# Nova_Placa.net
KiCad netlist of a schematic drawn in EAGLE
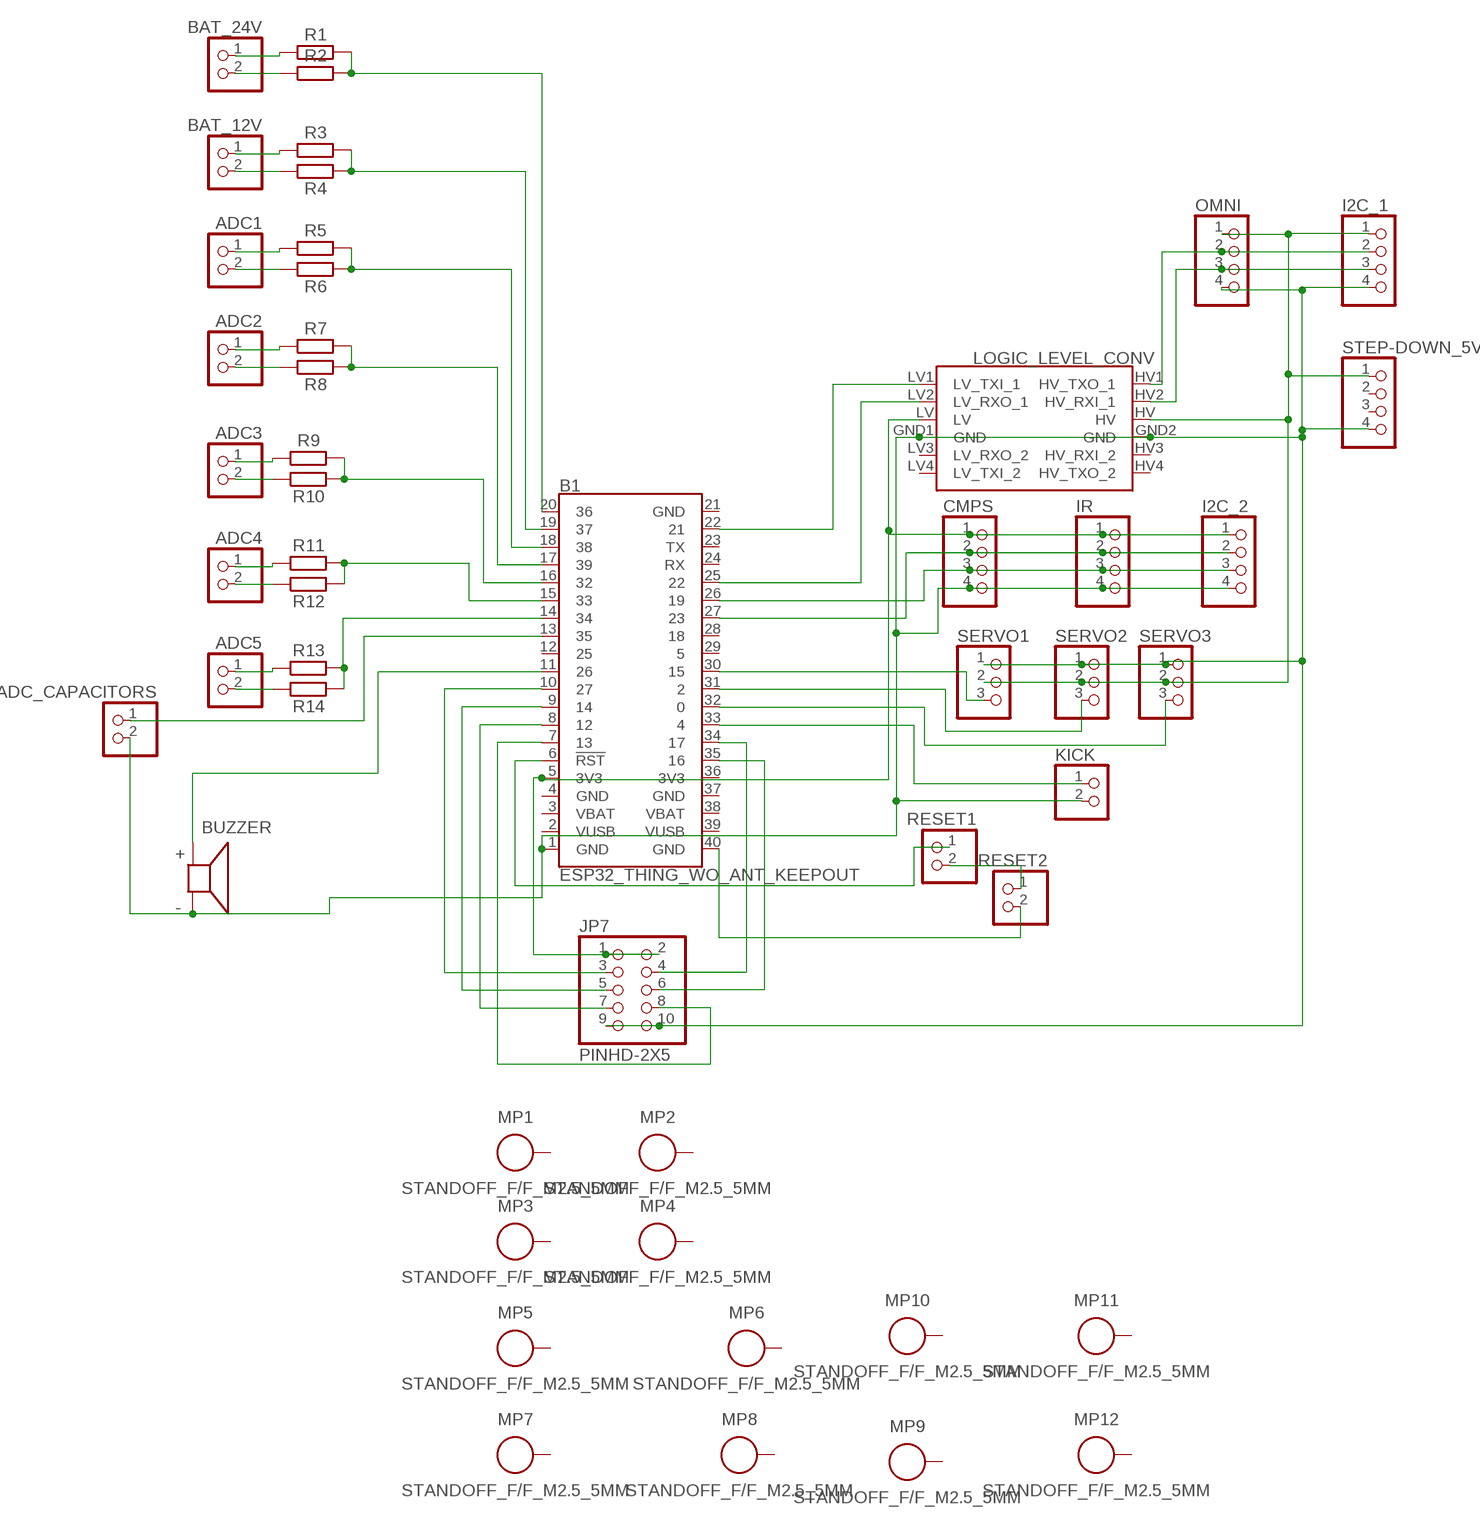
[diagram p0: schematic, sheet 1]

(export (version "E")
  (design (tool "Eeschema 10.0.6"))
  (components
    (comp (ref "ADC1")
      (value "PINHD-1X2")
      (footprint "eagle-import:1X02")
      (libsource (lib "eagle-import") (part "PINHD-1X2"))
    )
    (comp (ref "ADC2")
      (value "PINHD-1X2")
      (footprint "eagle-import:1X02")
      (libsource (lib "eagle-import") (part "PINHD-1X2"))
    )
    (comp (ref "ADC3")
      (value "PINHD-1X2")
      (footprint "eagle-import:1X02")
      (libsource (lib "eagle-import") (part "PINHD-1X2"))
    )
    (comp (ref "ADC4")
      (value "PINHD-1X2")
      (footprint "eagle-import:1X02")
      (libsource (lib "eagle-import") (part "PINHD-1X2"))
    )
    (comp (ref "ADC5")
      (value "PINHD-1X2")
      (footprint "eagle-import:1X02")
      (libsource (lib "eagle-import") (part "PINHD-1X2"))
    )
    (comp (ref "ADC_CAPACITORS")
      (value "PINHD-1X2")
      (footprint "eagle-import:1X02")
      (libsource (lib "eagle-import") (part "PINHD-1X2"))
    )
    (comp (ref "B1")
      (value "ESP32_THING_WO_ANT_KEEPOUT")
      (footprint "eagle-import:ESP32_THING_NO_ANT")
      (libsource (lib "eagle-import") (part "ESP32_THING_WO_ANT_KEEPOUT"))
    )
    (comp (ref "BAT_12V")
      (value "PINHD-1X2")
      (footprint "eagle-import:1X02")
      (libsource (lib "eagle-import") (part "PINHD-1X2"))
    )
    (comp (ref "BAT_24V")
      (value "PINHD-1X2")
      (footprint "eagle-import:1X02")
      (libsource (lib "eagle-import") (part "PINHD-1X2"))
    )
    (comp (ref "BUZZER")
      (value "AT-1220-TT-9-R")
      (footprint "eagle-import:XDCR_AT-1220-TT-9-R")
      (fields (field (name "MANUFACTURER") "PUI Audio"))
      (libsource (lib "eagle-import") (part "AT-1220-TT-9-R"))
    )
    (comp (ref "CMPS")
      (value "PINHD-1X4")
      (footprint "eagle-import:1X04")
      (libsource (lib "eagle-import") (part "PINHD-1X4"))
    )
    (comp (ref "I2C_1")
      (value "PINHD-1X4")
      (footprint "eagle-import:1X04")
      (libsource (lib "eagle-import") (part "PINHD-1X4"))
    )
    (comp (ref "I2C_2")
      (value "PINHD-1X4")
      (footprint "eagle-import:1X04")
      (libsource (lib "eagle-import") (part "PINHD-1X4"))
    )
    (comp (ref "IR")
      (value "PINHD-1X4")
      (footprint "eagle-import:1X04")
      (libsource (lib "eagle-import") (part "PINHD-1X4"))
    )
    (comp (ref "JP7")
      (value "PINHD-2X5")
      (footprint "eagle-import:2X05")
      (libsource (lib "eagle-import") (part "PINHD-2X5"))
    )
    (comp (ref "KICK")
      (value "PINHD-1X2")
      (footprint "eagle-import:1X02")
      (libsource (lib "eagle-import") (part "PINHD-1X2"))
    )
    (comp (ref "LOGIC_LEVEL_CONV")
      (value "SPARKFUN_LOGIC_LEVEL_CONVERTERLOCK")
      (footprint "eagle-import:SPARKFUN_LOGIC_LEVEL_CONVERTER_LOCK")
      (libsource (lib "eagle-import") (part "SPARKFUN_LOGIC_LEVEL_CONVERTERLOCK"))
    )
    (comp (ref "MP1")
      (value "STANDOFF_F/F_M2.5_5MM")
      (footprint "eagle-import:STANDOFF_HEX_FEMALE_500X500_M2.5X0.45_MTGP755H270")
      (libsource (lib "eagle-import") (part "STANDOFF_F/FM2.5_5MM_"))
    )
    (comp (ref "MP2")
      (value "STANDOFF_F/F_M2.5_5MM")
      (footprint "eagle-import:STANDOFF_HEX_FEMALE_500X500_M2.5X0.45_MTGP755H270")
      (libsource (lib "eagle-import") (part "STANDOFF_F/FM2.5_5MM_"))
    )
    (comp (ref "MP3")
      (value "STANDOFF_F/F_M2.5_5MM")
      (footprint "eagle-import:STANDOFF_HEX_FEMALE_500X500_M2.5X0.45_MTGP755H270")
      (libsource (lib "eagle-import") (part "STANDOFF_F/FM2.5_5MM_"))
    )
    (comp (ref "MP4")
      (value "STANDOFF_F/F_M2.5_5MM")
      (footprint "eagle-import:STANDOFF_HEX_FEMALE_500X500_M2.5X0.45_MTGP755H270")
      (libsource (lib "eagle-import") (part "STANDOFF_F/FM2.5_5MM_"))
    )
    (comp (ref "MP5")
      (value "STANDOFF_F/F_M2.5_5MM")
      (footprint "eagle-import:STANDOFF_HEX_FEMALE_500X500_M2.5X0.45_MTGP755H270")
      (libsource (lib "eagle-import") (part "STANDOFF_F/FM2.5_5MM_"))
    )
    (comp (ref "MP6")
      (value "STANDOFF_F/F_M2.5_5MM")
      (footprint "eagle-import:STANDOFF_HEX_FEMALE_500X500_M2.5X0.45_MTGP755H270")
      (libsource (lib "eagle-import") (part "STANDOFF_F/FM2.5_5MM_"))
    )
    (comp (ref "MP7")
      (value "STANDOFF_F/F_M2.5_5MM")
      (footprint "eagle-import:STANDOFF_HEX_FEMALE_500X500_M2.5X0.45_MTGP755H270")
      (libsource (lib "eagle-import") (part "STANDOFF_F/FM2.5_5MM_"))
    )
    (comp (ref "MP8")
      (value "STANDOFF_F/F_M2.5_5MM")
      (footprint "eagle-import:STANDOFF_HEX_FEMALE_500X500_M2.5X0.45_MTGP755H270")
      (libsource (lib "eagle-import") (part "STANDOFF_F/FM2.5_5MM_"))
    )
    (comp (ref "MP9")
      (value "STANDOFF_F/F_M2.5_5MM")
      (footprint "eagle-import:STANDOFF_HEX_FEMALE_500X500_M2.5X0.45_MTGP755H270")
      (libsource (lib "eagle-import") (part "STANDOFF_F/FM2.5_5MM_"))
    )
    (comp (ref "MP10")
      (value "STANDOFF_F/F_M2.5_5MM")
      (footprint "eagle-import:STANDOFF_HEX_FEMALE_500X500_M2.5X0.45_MTGP755H270")
      (libsource (lib "eagle-import") (part "STANDOFF_F/FM2.5_5MM_"))
    )
    (comp (ref "MP11")
      (value "STANDOFF_F/F_M2.5_5MM")
      (footprint "eagle-import:STANDOFF_HEX_FEMALE_500X500_M2.5X0.45_MTGP755H270")
      (libsource (lib "eagle-import") (part "STANDOFF_F/FM2.5_5MM_"))
    )
    (comp (ref "MP12")
      (value "STANDOFF_F/F_M2.5_5MM")
      (footprint "eagle-import:STANDOFF_HEX_FEMALE_500X500_M2.5X0.45_MTGP755H270")
      (libsource (lib "eagle-import") (part "STANDOFF_F/FM2.5_5MM_"))
    )
    (comp (ref "OMNI")
      (value "PINHD-1X4")
      (footprint "eagle-import:1X04")
      (libsource (lib "eagle-import") (part "PINHD-1X4"))
    )
    (comp (ref "R1")
      (value "R_AXIAL-7.2MM-PITCH")
      (footprint "eagle-import:RESAD724W46L381D178B")
      (libsource (lib "eagle-import") (part "RAXIAL-7.2MM-PITCH_"))
    )
    (comp (ref "R2")
      (value "R_AXIAL-7.2MM-PITCH")
      (footprint "eagle-import:RESAD724W46L381D178B")
      (libsource (lib "eagle-import") (part "RAXIAL-7.2MM-PITCH_"))
    )
    (comp (ref "R3")
      (value "R_AXIAL-7.2MM-PITCH")
      (footprint "eagle-import:RESAD724W46L381D178B")
      (libsource (lib "eagle-import") (part "RAXIAL-7.2MM-PITCH_"))
    )
    (comp (ref "R4")
      (value "R_AXIAL-7.2MM-PITCH")
      (footprint "eagle-import:RESAD724W46L381D178B")
      (libsource (lib "eagle-import") (part "RAXIAL-7.2MM-PITCH_"))
    )
    (comp (ref "R5")
      (value "R_AXIAL-7.2MM-PITCH")
      (footprint "eagle-import:RESAD724W46L381D178B")
      (libsource (lib "eagle-import") (part "RAXIAL-7.2MM-PITCH_"))
    )
    (comp (ref "R6")
      (value "R_AXIAL-7.2MM-PITCH")
      (footprint "eagle-import:RESAD724W46L381D178B")
      (libsource (lib "eagle-import") (part "RAXIAL-7.2MM-PITCH_"))
    )
    (comp (ref "R7")
      (value "R_AXIAL-7.2MM-PITCH")
      (footprint "eagle-import:RESAD724W46L381D178B")
      (libsource (lib "eagle-import") (part "RAXIAL-7.2MM-PITCH_"))
    )
    (comp (ref "R8")
      (value "R_AXIAL-7.2MM-PITCH")
      (footprint "eagle-import:RESAD724W46L381D178B")
      (libsource (lib "eagle-import") (part "RAXIAL-7.2MM-PITCH_"))
    )
    (comp (ref "R9")
      (value "R_AXIAL-7.2MM-PITCH")
      (footprint "eagle-import:RESAD724W46L381D178B")
      (libsource (lib "eagle-import") (part "RAXIAL-7.2MM-PITCH_"))
    )
    (comp (ref "R10")
      (value "R_AXIAL-7.2MM-PITCH")
      (footprint "eagle-import:RESAD724W46L381D178B")
      (libsource (lib "eagle-import") (part "RAXIAL-7.2MM-PITCH_"))
    )
    (comp (ref "R11")
      (value "R_AXIAL-7.2MM-PITCH")
      (footprint "eagle-import:RESAD724W46L381D178B")
      (libsource (lib "eagle-import") (part "RAXIAL-7.2MM-PITCH_"))
    )
    (comp (ref "R12")
      (value "R_AXIAL-7.2MM-PITCH")
      (footprint "eagle-import:RESAD724W46L381D178B")
      (libsource (lib "eagle-import") (part "RAXIAL-7.2MM-PITCH_"))
    )
    (comp (ref "R13")
      (value "R_AXIAL-7.2MM-PITCH")
      (footprint "eagle-import:RESAD724W46L381D178B")
      (libsource (lib "eagle-import") (part "RAXIAL-7.2MM-PITCH_"))
    )
    (comp (ref "R14")
      (value "R_AXIAL-7.2MM-PITCH")
      (footprint "eagle-import:RESAD724W46L381D178B")
      (libsource (lib "eagle-import") (part "RAXIAL-7.2MM-PITCH_"))
    )
    (comp (ref "RESET1")
      (value "PINHD-1X2")
      (footprint "eagle-import:1X02")
      (libsource (lib "eagle-import") (part "PINHD-1X2"))
    )
    (comp (ref "RESET2")
      (value "PINHD-1X2")
      (footprint "eagle-import:1X02")
      (libsource (lib "eagle-import") (part "PINHD-1X2"))
    )
    (comp (ref "SERVO1")
      (value "PINHD-1X3")
      (footprint "eagle-import:1X03")
      (libsource (lib "eagle-import") (part "PINHD-1X3"))
    )
    (comp (ref "SERVO2")
      (value "PINHD-1X3")
      (footprint "eagle-import:1X03")
      (libsource (lib "eagle-import") (part "PINHD-1X3"))
    )
    (comp (ref "SERVO3")
      (value "PINHD-1X3")
      (footprint "eagle-import:1X03")
      (libsource (lib "eagle-import") (part "PINHD-1X3"))
    )
    (comp (ref "STEP-DOWN_5V")
      (value "PINHD-1X4")
      (footprint "eagle-import:1X04")
      (libsource (lib "eagle-import") (part "PINHD-1X4"))
    )
  )
  (nets
    (net (code "1") (name "Net-(ADC1-Pad1)") (class "Default")
      (node (ref "ADC1") (pin "1") (pinfunction "1_1") (pintype "passive"))
      (node (ref "R5") (pin "1") (pinfunction "1_1") (pintype "passive"))
    )
    (net (code "2") (name "Net-(ADC1-Pad2)") (class "Default")
      (node (ref "ADC1") (pin "2") (pinfunction "2_2") (pintype "passive"))
      (node (ref "R6") (pin "1") (pinfunction "1_1") (pintype "passive"))
    )
    (net (code "3") (name "Net-(ADC2-Pad1)") (class "Default")
      (node (ref "ADC2") (pin "1") (pinfunction "1_1") (pintype "passive"))
      (node (ref "R7") (pin "1") (pinfunction "1_1") (pintype "passive"))
    )
    (net (code "4") (name "Net-(ADC2-Pad2)") (class "Default")
      (node (ref "ADC2") (pin "2") (pinfunction "2_2") (pintype "passive"))
      (node (ref "R8") (pin "1") (pinfunction "1_1") (pintype "passive"))
    )
    (net (code "5") (name "Net-(ADC3-Pad1)") (class "Default")
      (node (ref "ADC3") (pin "1") (pinfunction "1_1") (pintype "passive"))
      (node (ref "R9") (pin "1") (pinfunction "1_1") (pintype "passive"))
    )
    (net (code "6") (name "Net-(ADC3-Pad2)") (class "Default")
      (node (ref "ADC3") (pin "2") (pinfunction "2_2") (pintype "passive"))
      (node (ref "R10") (pin "1") (pinfunction "1_1") (pintype "passive"))
    )
    (net (code "7") (name "Net-(ADC4-Pad1)") (class "Default")
      (node (ref "ADC4") (pin "1") (pinfunction "1_1") (pintype "passive"))
      (node (ref "R11") (pin "1") (pinfunction "1_1") (pintype "passive"))
    )
    (net (code "8") (name "Net-(ADC4-Pad2)") (class "Default")
      (node (ref "ADC4") (pin "2") (pinfunction "2_2") (pintype "passive"))
      (node (ref "R12") (pin "1") (pinfunction "1_1") (pintype "passive"))
    )
    (net (code "9") (name "Net-(ADC5-Pad1)") (class "Default")
      (node (ref "ADC5") (pin "1") (pinfunction "1_1") (pintype "passive"))
      (node (ref "R13") (pin "1") (pinfunction "1_1") (pintype "passive"))
    )
    (net (code "10") (name "Net-(ADC5-Pad2)") (class "Default")
      (node (ref "ADC5") (pin "2") (pinfunction "2_2") (pintype "passive"))
      (node (ref "R14") (pin "1") (pinfunction "1_1") (pintype "passive"))
    )
    (net (code "11") (name "Net-(ADC_CAPACITORS-Pad2)") (class "Default")
      (node (ref "ADC_CAPACITORS") (pin "2") (pinfunction "2_2") (pintype "passive"))
      (node (ref "B1") (pin "1") (pinfunction "GND_1") (pintype "bidirectional"))
      (node (ref "BUZZER") (pin "N") (pinfunction "N_N") (pintype "passive"))
      (node (ref "CMPS") (pin "4") (pinfunction "4_4") (pintype "passive"))
      (node (ref "I2C_1") (pin "4") (pinfunction "4_4") (pintype "passive"))
      (node (ref "I2C_2") (pin "4") (pinfunction "4_4") (pintype "passive"))
      (node (ref "IR") (pin "4") (pinfunction "4_4") (pintype "passive"))
      (node (ref "JP7") (pin "10") (pinfunction "10_10") (pintype "passive"))
      (node (ref "JP7") (pin "9") (pinfunction "9_9") (pintype "passive"))
      (node (ref "KICK") (pin "2") (pinfunction "2_2") (pintype "passive"))
      (node (ref "LOGIC_LEVEL_CONV") (pin "GND1") (pinfunction "GND_GND1") (pintype "power_in"))
      (node (ref "LOGIC_LEVEL_CONV") (pin "GND2") (pinfunction "GND_GND2") (pintype "power_in"))
      (node (ref "OMNI") (pin "4") (pinfunction "4_4") (pintype "passive"))
      (node (ref "SERVO1") (pin "1") (pinfunction "1_1") (pintype "passive"))
      (node (ref "SERVO2") (pin "1") (pinfunction "1_1") (pintype "passive"))
      (node (ref "SERVO3") (pin "1") (pinfunction "1_1") (pintype "passive"))
      (node (ref "STEP-DOWN_5V") (pin "4") (pinfunction "4_4") (pintype "passive"))
    )
    (net (code "12") (name "Net-(B1-0)") (class "Default")
      (node (ref "B1") (pin "32") (pinfunction "0_32") (pintype "bidirectional"))
      (node (ref "SERVO3") (pin "3") (pinfunction "3_3") (pintype "passive"))
    )
    (net (code "13") (name "Net-(B1-2)") (class "Default")
      (node (ref "B1") (pin "31") (pinfunction "2_31") (pintype "bidirectional"))
      (node (ref "SERVO2") (pin "3") (pinfunction "3_3") (pintype "passive"))
    )
    (net (code "14") (name "Net-(B1-3V3-Pad5)") (class "Default")
      (node (ref "B1") (pin "5") (pinfunction "3V3_5") (pintype "bidirectional"))
      (node (ref "CMPS") (pin "1") (pinfunction "1_1") (pintype "passive"))
      (node (ref "I2C_2") (pin "1") (pinfunction "1_1") (pintype "passive"))
      (node (ref "IR") (pin "1") (pinfunction "1_1") (pintype "passive"))
      (node (ref "JP7") (pin "1") (pinfunction "1_1") (pintype "passive"))
      (node (ref "JP7") (pin "2") (pinfunction "2_2") (pintype "passive"))
      (node (ref "LOGIC_LEVEL_CONV") (pin "LV") (pinfunction "LV_LV") (pintype "power_in"))
    )
    (net (code "15") (name "Net-(B1-4)") (class "Default")
      (node (ref "B1") (pin "33") (pinfunction "4_33") (pintype "bidirectional"))
      (node (ref "KICK") (pin "1") (pinfunction "1_1") (pintype "passive"))
    )
    (net (code "16") (name "Net-(B1-12)") (class "Default")
      (node (ref "B1") (pin "8") (pinfunction "12_8") (pintype "bidirectional"))
      (node (ref "JP7") (pin "7") (pinfunction "7_7") (pintype "passive"))
    )
    (net (code "17") (name "Net-(B1-13)") (class "Default")
      (node (ref "B1") (pin "7") (pinfunction "13_7") (pintype "bidirectional"))
      (node (ref "JP7") (pin "8") (pinfunction "8_8") (pintype "passive"))
    )
    (net (code "18") (name "Net-(B1-14)") (class "Default")
      (node (ref "B1") (pin "9") (pinfunction "14_9") (pintype "bidirectional"))
      (node (ref "JP7") (pin "5") (pinfunction "5_5") (pintype "passive"))
    )
    (net (code "19") (name "Net-(B1-15)") (class "Default")
      (node (ref "B1") (pin "30") (pinfunction "15_30") (pintype "bidirectional"))
      (node (ref "SERVO1") (pin "3") (pinfunction "3_3") (pintype "passive"))
    )
    (net (code "20") (name "Net-(B1-16)") (class "Default")
      (node (ref "B1") (pin "35") (pinfunction "16_35") (pintype "bidirectional"))
      (node (ref "JP7") (pin "6") (pinfunction "6_6") (pintype "passive"))
    )
    (net (code "21") (name "Net-(B1-17)") (class "Default")
      (node (ref "B1") (pin "34") (pinfunction "17_34") (pintype "bidirectional"))
      (node (ref "JP7") (pin "4") (pinfunction "4_4") (pintype "passive"))
    )
    (net (code "22") (name "Net-(B1-19)") (class "Default")
      (node (ref "B1") (pin "26") (pinfunction "19_26") (pintype "bidirectional"))
      (node (ref "CMPS") (pin "3") (pinfunction "3_3") (pintype "passive"))
      (node (ref "I2C_2") (pin "3") (pinfunction "3_3") (pintype "passive"))
      (node (ref "IR") (pin "3") (pinfunction "3_3") (pintype "passive"))
    )
    (net (code "23") (name "Net-(B1-21)") (class "Default")
      (node (ref "B1") (pin "22") (pinfunction "21_22") (pintype "bidirectional"))
      (node (ref "LOGIC_LEVEL_CONV") (pin "LV1") (pinfunction "LV_TXI_1_LV1") (pintype "bidirectional"))
    )
    (net (code "24") (name "Net-(B1-22)") (class "Default")
      (node (ref "B1") (pin "25") (pinfunction "22_25") (pintype "bidirectional"))
      (node (ref "LOGIC_LEVEL_CONV") (pin "LV2") (pinfunction "LV_RXO_1_LV2") (pintype "bidirectional"))
    )
    (net (code "25") (name "Net-(B1-23)") (class "Default")
      (node (ref "B1") (pin "27") (pinfunction "23_27") (pintype "bidirectional"))
      (node (ref "CMPS") (pin "2") (pinfunction "2_2") (pintype "passive"))
      (node (ref "I2C_2") (pin "2") (pinfunction "2_2") (pintype "passive"))
      (node (ref "IR") (pin "2") (pinfunction "2_2") (pintype "passive"))
    )
    (net (code "26") (name "Net-(B1-26)") (class "Default")
      (node (ref "B1") (pin "11") (pinfunction "26_11") (pintype "bidirectional"))
      (node (ref "BUZZER") (pin "P") (pinfunction "P_P") (pintype "passive"))
    )
    (net (code "27") (name "Net-(B1-27)") (class "Default")
      (node (ref "B1") (pin "10") (pinfunction "27_10") (pintype "bidirectional"))
      (node (ref "JP7") (pin "3") (pinfunction "3_3") (pintype "passive"))
    )
    (net (code "28") (name "Net-(B1-32)") (class "Default")
      (node (ref "B1") (pin "16") (pinfunction "32_16") (pintype "bidirectional"))
      (node (ref "R10") (pin "2") (pinfunction "2_2") (pintype "passive"))
      (node (ref "R9") (pin "2") (pinfunction "2_2") (pintype "passive"))
    )
    (net (code "29") (name "Net-(B1-33)") (class "Default")
      (node (ref "B1") (pin "15") (pinfunction "33_15") (pintype "bidirectional"))
      (node (ref "R11") (pin "2") (pinfunction "2_2") (pintype "passive"))
      (node (ref "R12") (pin "2") (pinfunction "2_2") (pintype "passive"))
    )
    (net (code "30") (name "Net-(B1-34)") (class "Default")
      (node (ref "B1") (pin "14") (pinfunction "34_14") (pintype "bidirectional"))
      (node (ref "R13") (pin "2") (pinfunction "2_2") (pintype "passive"))
      (node (ref "R14") (pin "2") (pinfunction "2_2") (pintype "passive"))
    )
    (net (code "31") (name "Net-(B1-35)") (class "Default")
      (node (ref "ADC_CAPACITORS") (pin "1") (pinfunction "1_1") (pintype "passive"))
      (node (ref "B1") (pin "13") (pinfunction "35_13") (pintype "bidirectional"))
    )
    (net (code "32") (name "Net-(B1-36)") (class "Default")
      (node (ref "B1") (pin "20") (pinfunction "36_20") (pintype "bidirectional"))
      (node (ref "R1") (pin "2") (pinfunction "2_2") (pintype "passive"))
      (node (ref "R2") (pin "2") (pinfunction "2_2") (pintype "passive"))
    )
    (net (code "33") (name "Net-(B1-37)") (class "Default")
      (node (ref "B1") (pin "19") (pinfunction "37_19") (pintype "bidirectional"))
      (node (ref "R3") (pin "2") (pinfunction "2_2") (pintype "passive"))
      (node (ref "R4") (pin "2") (pinfunction "2_2") (pintype "passive"))
    )
    (net (code "34") (name "Net-(B1-38)") (class "Default")
      (node (ref "B1") (pin "18") (pinfunction "38_18") (pintype "bidirectional"))
      (node (ref "R5") (pin "2") (pinfunction "2_2") (pintype "passive"))
      (node (ref "R6") (pin "2") (pinfunction "2_2") (pintype "passive"))
    )
    (net (code "35") (name "Net-(B1-39)") (class "Default")
      (node (ref "B1") (pin "17") (pinfunction "39_17") (pintype "bidirectional"))
      (node (ref "R7") (pin "2") (pinfunction "2_2") (pintype "passive"))
      (node (ref "R8") (pin "2") (pinfunction "2_2") (pintype "passive"))
    )
    (net (code "36") (name "Net-(B1-GND-Pad40)") (class "Default")
      (node (ref "B1") (pin "40") (pinfunction "GND_40") (pintype "bidirectional"))
      (node (ref "RESET2") (pin "2") (pinfunction "2_2") (pintype "passive"))
    )
    (net (code "37") (name "Net-(B1-~{RST})") (class "Default")
      (node (ref "B1") (pin "6") (pinfunction "~{RST}_6") (pintype "bidirectional"))
      (node (ref "RESET1") (pin "1") (pinfunction "1_1") (pintype "passive"))
    )
    (net (code "38") (name "Net-(BAT_12V-Pad1)") (class "Default")
      (node (ref "BAT_12V") (pin "1") (pinfunction "1_1") (pintype "passive"))
      (node (ref "R3") (pin "1") (pinfunction "1_1") (pintype "passive"))
    )
    (net (code "39") (name "Net-(BAT_12V-Pad2)") (class "Default")
      (node (ref "BAT_12V") (pin "2") (pinfunction "2_2") (pintype "passive"))
      (node (ref "R4") (pin "1") (pinfunction "1_1") (pintype "passive"))
    )
    (net (code "40") (name "Net-(BAT_24V-Pad1)") (class "Default")
      (node (ref "BAT_24V") (pin "1") (pinfunction "1_1") (pintype "passive"))
      (node (ref "R1") (pin "1") (pinfunction "1_1") (pintype "passive"))
    )
    (net (code "41") (name "Net-(BAT_24V-Pad2)") (class "Default")
      (node (ref "BAT_24V") (pin "2") (pinfunction "2_2") (pintype "passive"))
      (node (ref "R2") (pin "1") (pinfunction "1_1") (pintype "passive"))
    )
    (net (code "42") (name "Net-(I2C_1-Pad1)") (class "Default")
      (node (ref "I2C_1") (pin "1") (pinfunction "1_1") (pintype "passive"))
      (node (ref "LOGIC_LEVEL_CONV") (pin "HV") (pinfunction "HV_HV") (pintype "power_in"))
      (node (ref "OMNI") (pin "1") (pinfunction "1_1") (pintype "passive"))
      (node (ref "SERVO1") (pin "2") (pinfunction "2_2") (pintype "passive"))
      (node (ref "SERVO2") (pin "2") (pinfunction "2_2") (pintype "passive"))
      (node (ref "SERVO3") (pin "2") (pinfunction "2_2") (pintype "passive"))
      (node (ref "STEP-DOWN_5V") (pin "1") (pinfunction "1_1") (pintype "passive"))
    )
    (net (code "43") (name "Net-(LOGIC_LEVEL_CONV-HV_RXI_1)") (class "Default")
      (node (ref "I2C_1") (pin "3") (pinfunction "3_3") (pintype "passive"))
      (node (ref "LOGIC_LEVEL_CONV") (pin "HV2") (pinfunction "HV_RXI_1_HV2") (pintype "bidirectional"))
      (node (ref "OMNI") (pin "3") (pinfunction "3_3") (pintype "passive"))
    )
    (net (code "44") (name "Net-(LOGIC_LEVEL_CONV-HV_TXO_1)") (class "Default")
      (node (ref "I2C_1") (pin "2") (pinfunction "2_2") (pintype "passive"))
      (node (ref "LOGIC_LEVEL_CONV") (pin "HV1") (pinfunction "HV_TXO_1_HV1") (pintype "bidirectional"))
      (node (ref "OMNI") (pin "2") (pinfunction "2_2") (pintype "passive"))
    )
    (net (code "45") (name "Net-(RESET1-Pad2)") (class "Default")
      (node (ref "RESET1") (pin "2") (pinfunction "2_2") (pintype "passive"))
      (node (ref "RESET2") (pin "1") (pinfunction "1_1") (pintype "passive"))
    )
    (net (code "46") (name "unconnected-(B1-3V3-Pad36)") (class "Default")
      (node (ref "B1") (pin "36") (pinfunction "3V3_36") (pintype "bidirectional"))
    )
    (net (code "47") (name "unconnected-(B1-5-Pad29)") (class "Default")
      (node (ref "B1") (pin "29") (pinfunction "5_29") (pintype "bidirectional"))
    )
    (net (code "48") (name "unconnected-(B1-18-Pad28)") (class "Default")
      (node (ref "B1") (pin "28") (pinfunction "18_28") (pintype "bidirectional"))
    )
    (net (code "49") (name "unconnected-(B1-25-Pad12)") (class "Default")
      (node (ref "B1") (pin "12") (pinfunction "25_12") (pintype "bidirectional"))
    )
    (net (code "50") (name "unconnected-(B1-GND-Pad4)") (class "Default")
      (node (ref "B1") (pin "4") (pinfunction "GND_4") (pintype "bidirectional"))
    )
    (net (code "51") (name "unconnected-(B1-GND-Pad21)") (class "Default")
      (node (ref "B1") (pin "21") (pinfunction "GND_21") (pintype "bidirectional"))
    )
    (net (code "52") (name "unconnected-(B1-GND-Pad37)") (class "Default")
      (node (ref "B1") (pin "37") (pinfunction "GND_37") (pintype "bidirectional"))
    )
    (net (code "53") (name "unconnected-(B1-RX-Pad24)") (class "Default")
      (node (ref "B1") (pin "24") (pinfunction "RX_24") (pintype "bidirectional"))
    )
    (net (code "54") (name "unconnected-(B1-TX-Pad23)") (class "Default")
      (node (ref "B1") (pin "23") (pinfunction "TX_23") (pintype "bidirectional"))
    )
    (net (code "55") (name "unconnected-(B1-VBAT-Pad3)") (class "Default")
      (node (ref "B1") (pin "3") (pinfunction "VBAT_3") (pintype "bidirectional"))
    )
    (net (code "56") (name "unconnected-(B1-VBAT-Pad38)") (class "Default")
      (node (ref "B1") (pin "38") (pinfunction "VBAT_38") (pintype "bidirectional"))
    )
    (net (code "57") (name "unconnected-(B1-VUSB-Pad2)") (class "Default")
      (node (ref "B1") (pin "2") (pinfunction "VUSB_2") (pintype "bidirectional"))
    )
    (net (code "58") (name "unconnected-(B1-VUSB-Pad39)") (class "Default")
      (node (ref "B1") (pin "39") (pinfunction "VUSB_39") (pintype "bidirectional"))
    )
    (net (code "59") (name "unconnected-(LOGIC_LEVEL_CONV-HV_RXI_2-PadHV3)") (class "Default")
      (node (ref "LOGIC_LEVEL_CONV") (pin "HV3") (pinfunction "HV_RXI_2_HV3") (pintype "bidirectional"))
    )
    (net (code "60") (name "unconnected-(LOGIC_LEVEL_CONV-HV_TXO_2-PadHV4)") (class "Default")
      (node (ref "LOGIC_LEVEL_CONV") (pin "HV4") (pinfunction "HV_TXO_2_HV4") (pintype "bidirectional"))
    )
    (net (code "61") (name "unconnected-(LOGIC_LEVEL_CONV-LV_RXO_2-PadLV3)") (class "Default")
      (node (ref "LOGIC_LEVEL_CONV") (pin "LV3") (pinfunction "LV_RXO_2_LV3") (pintype "bidirectional"))
    )
    (net (code "62") (name "unconnected-(LOGIC_LEVEL_CONV-LV_TXI_2-PadLV4)") (class "Default")
      (node (ref "LOGIC_LEVEL_CONV") (pin "LV4") (pinfunction "LV_TXI_2_LV4") (pintype "bidirectional"))
    )
    (net (code "63") (name "unconnected-(MP1-P$1-Pad1)") (class "Default")
      (node (ref "MP1") (pin "1") (pinfunction "P$1_1") (pintype "passive"))
    )
    (net (code "64") (name "unconnected-(MP2-P$1-Pad1)") (class "Default")
      (node (ref "MP2") (pin "1") (pinfunction "P$1_1") (pintype "passive"))
    )
    (net (code "65") (name "unconnected-(MP3-P$1-Pad1)") (class "Default")
      (node (ref "MP3") (pin "1") (pinfunction "P$1_1") (pintype "passive"))
    )
    (net (code "66") (name "unconnected-(MP4-P$1-Pad1)") (class "Default")
      (node (ref "MP4") (pin "1") (pinfunction "P$1_1") (pintype "passive"))
    )
    (net (code "67") (name "unconnected-(MP5-P$1-Pad1)") (class "Default")
      (node (ref "MP5") (pin "1") (pinfunction "P$1_1") (pintype "passive"))
    )
    (net (code "68") (name "unconnected-(MP6-P$1-Pad1)") (class "Default")
      (node (ref "MP6") (pin "1") (pinfunction "P$1_1") (pintype "passive"))
    )
    (net (code "69") (name "unconnected-(MP7-P$1-Pad1)") (class "Default")
      (node (ref "MP7") (pin "1") (pinfunction "P$1_1") (pintype "passive"))
    )
    (net (code "70") (name "unconnected-(MP8-P$1-Pad1)") (class "Default")
      (node (ref "MP8") (pin "1") (pinfunction "P$1_1") (pintype "passive"))
    )
    (net (code "71") (name "unconnected-(MP9-P$1-Pad1)") (class "Default")
      (node (ref "MP9") (pin "1") (pinfunction "P$1_1") (pintype "passive"))
    )
    (net (code "72") (name "unconnected-(MP10-P$1-Pad1)") (class "Default")
      (node (ref "MP10") (pin "1") (pinfunction "P$1_1") (pintype "passive"))
    )
    (net (code "73") (name "unconnected-(MP11-P$1-Pad1)") (class "Default")
      (node (ref "MP11") (pin "1") (pinfunction "P$1_1") (pintype "passive"))
    )
    (net (code "74") (name "unconnected-(MP12-P$1-Pad1)") (class "Default")
      (node (ref "MP12") (pin "1") (pinfunction "P$1_1") (pintype "passive"))
    )
    (net (code "75") (name "unconnected-(STEP-DOWN_5V-Pad2)") (class "Default")
      (node (ref "STEP-DOWN_5V") (pin "2") (pinfunction "2_2") (pintype "passive"))
    )
    (net (code "76") (name "unconnected-(STEP-DOWN_5V-Pad3)") (class "Default")
      (node (ref "STEP-DOWN_5V") (pin "3") (pinfunction "3_3") (pintype "passive"))
    )
  )
)
